# M306X.net
KiCad netlist of a schematic drawn in EAGLE
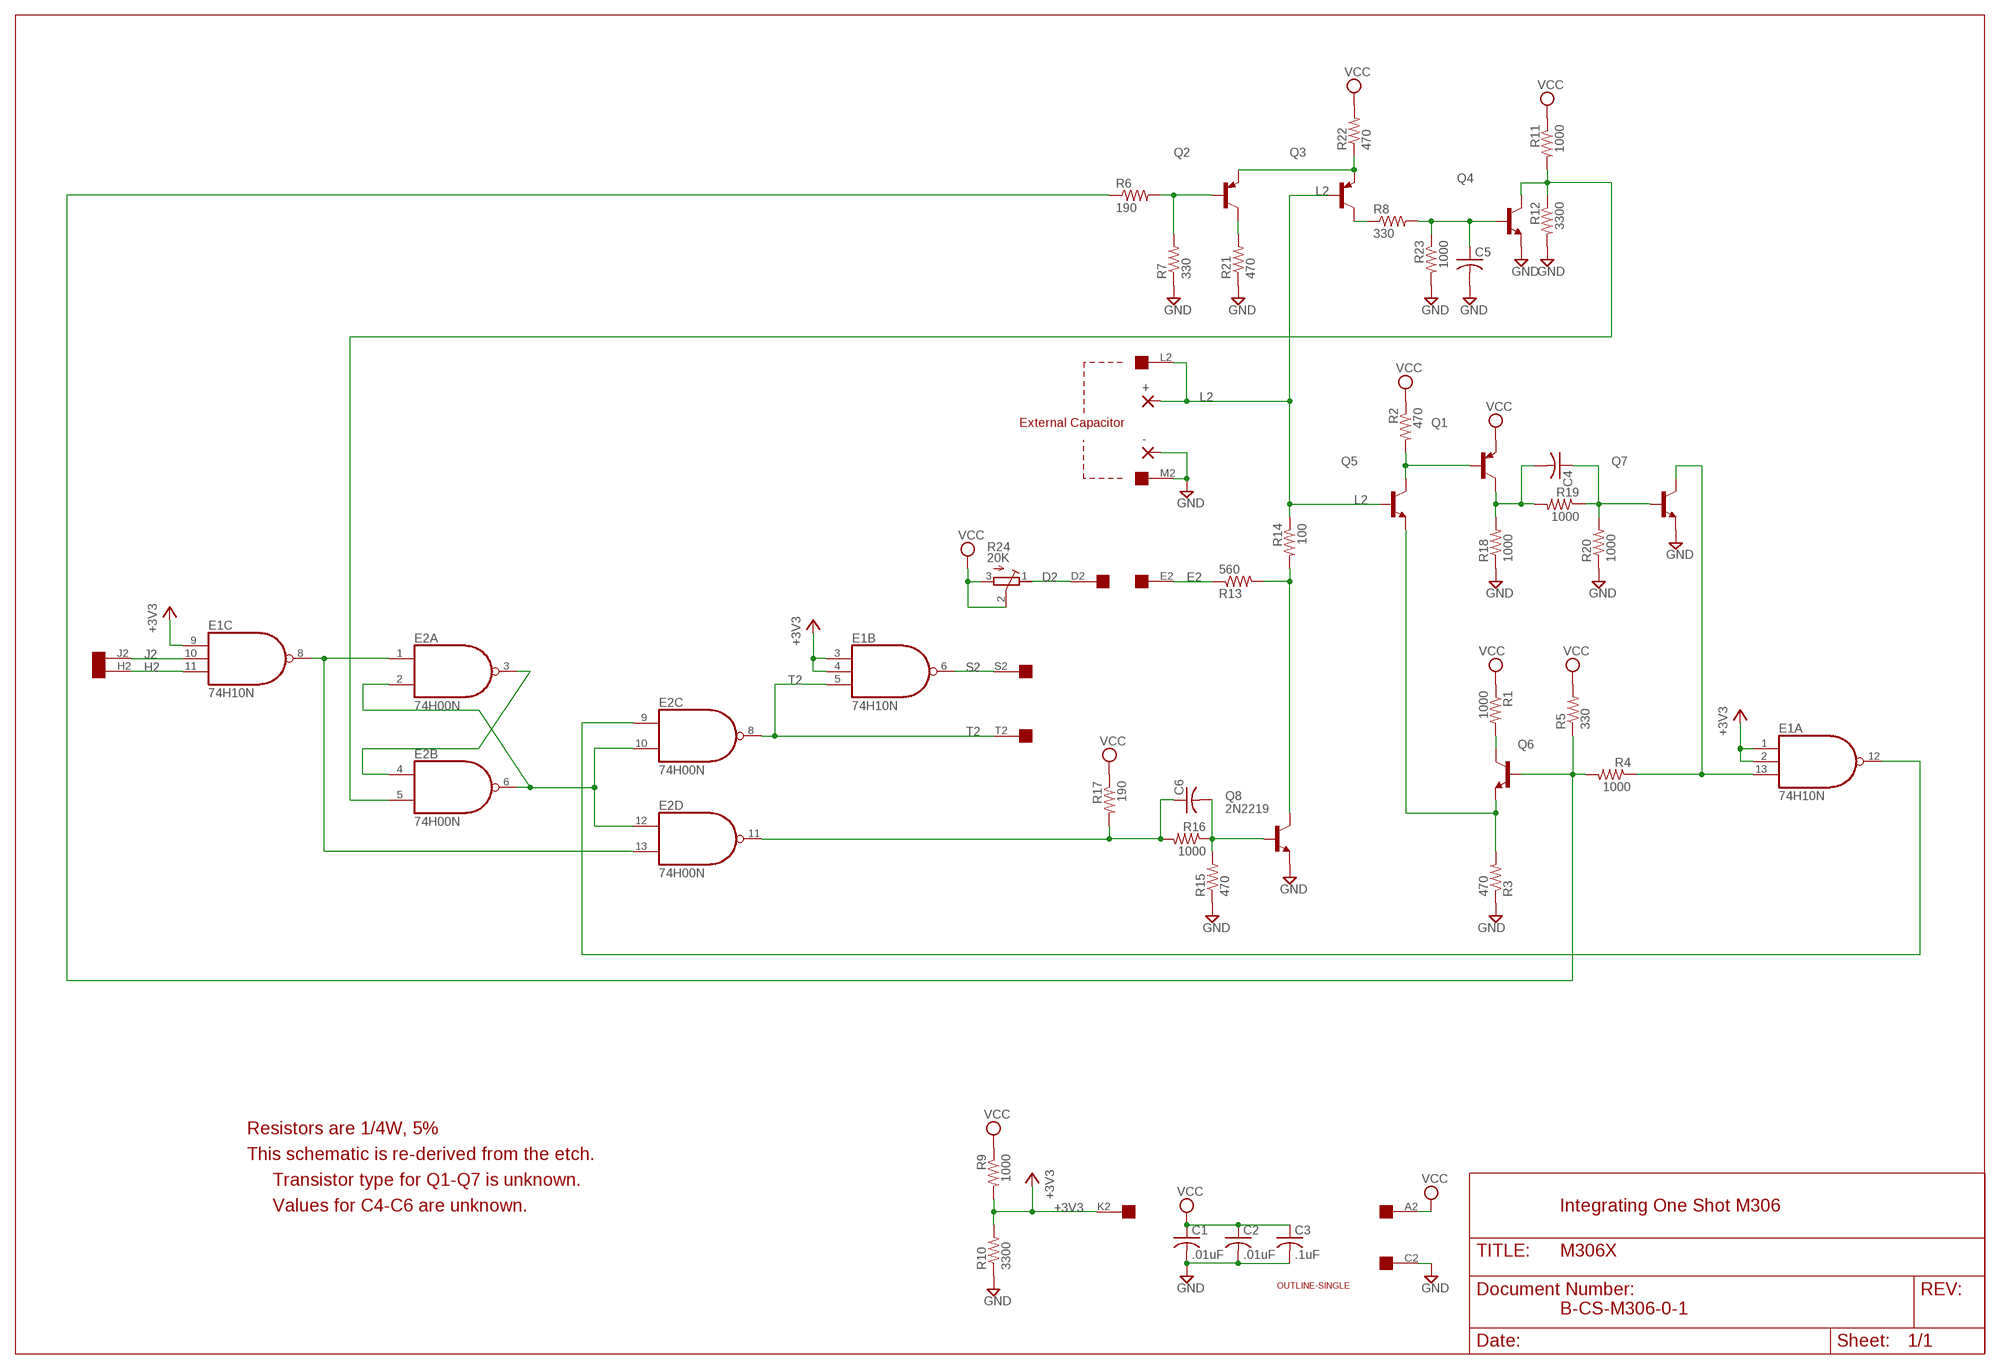
[diagram p0: schematic, sheet 1]

(export (version "E")
  (design (tool "Eeschema 10.0.6"))
  (components
    (comp (ref "+")
      (value "3,17/1,3")
      (footprint "eagle-import:3,17_1,3")
      (libsource (lib "eagle-import") (part "3,17/1,3"))
    )
    (comp (ref "-")
      (value "3,17/1,3")
      (footprint "eagle-import:3,17_1,3")
      (libsource (lib "eagle-import") (part "3,17/1,3"))
    )
    (comp (ref "C1")
      (value ".01uF")
      (footprint "eagle-import:C050-025X075")
      (libsource (lib "eagle-import") (part "C-US050-025X075"))
    )
    (comp (ref "C2")
      (value ".01uF")
      (footprint "eagle-import:C050-025X075")
      (libsource (lib "eagle-import") (part "C-US050-025X075"))
    )
    (comp (ref "C3")
      (value ".1uF")
      (footprint "eagle-import:C102-043X133")
      (libsource (lib "eagle-import") (part "C-US102-043X133"))
    )
    (comp (ref "C4")
      (value "C-US075-032X103")
      (footprint "eagle-import:C075-032X103")
      (libsource (lib "eagle-import") (part "C-US075-032X103"))
    )
    (comp (ref "C5")
      (value "C-US075-032X103")
      (footprint "eagle-import:C075-032X103")
      (libsource (lib "eagle-import") (part "C-US075-032X103"))
    )
    (comp (ref "C6")
      (value "C-US075-032X103")
      (footprint "eagle-import:C075-032X103")
      (libsource (lib "eagle-import") (part "C-US075-032X103"))
    )
    (comp (ref "E1")
      (value "74H10N")
      (footprint "eagle-import:DIL14")
      (libsource (lib "eagle-import") (part "7410N"))
    )
    (comp (ref "E2")
      (value "74H00N")
      (footprint "eagle-import:DIL14")
      (libsource (lib "eagle-import") (part "7400N"))
    )
    (comp (ref "Q1")
      (value "-PNP-TO5")
      (footprint "eagle-import:TO5")
      (libsource (lib "eagle-import") (part "-PNP-TO5"))
    )
    (comp (ref "Q2")
      (value "-PNP-TO5")
      (footprint "eagle-import:TO5")
      (libsource (lib "eagle-import") (part "-PNP-TO5"))
    )
    (comp (ref "Q3")
      (value "-PNP-TO5")
      (footprint "eagle-import:TO5")
      (libsource (lib "eagle-import") (part "-PNP-TO5"))
    )
    (comp (ref "Q4")
      (value "2N3019-NPN-TO39-EBC")
      (footprint "eagle-import:TO39")
      (libsource (lib "eagle-import") (part "-NPN-TO39-EBC2N3019"))
    )
    (comp (ref "Q5")
      (value "2N3019-NPN-TO39-EBC")
      (footprint "eagle-import:TO39")
      (libsource (lib "eagle-import") (part "-NPN-TO39-EBC2N3019"))
    )
    (comp (ref "Q6")
      (value "2N3019-NPN-TO39-EBC")
      (footprint "eagle-import:TO39")
      (libsource (lib "eagle-import") (part "-NPN-TO39-EBC2N3019"))
    )
    (comp (ref "Q7")
      (value "2N3019-NPN-TO39-EBC")
      (footprint "eagle-import:TO39")
      (libsource (lib "eagle-import") (part "-NPN-TO39-EBC2N3019"))
    )
    (comp (ref "Q8")
      (value "2N2219")
      (footprint "eagle-import:TO5")
      (libsource (lib "eagle-import") (part "2N2219"))
    )
    (comp (ref "R1")
      (value "1000")
      (footprint "eagle-import:0207_10")
      (libsource (lib "eagle-import") (part "R-US_0207/10"))
    )
    (comp (ref "R2")
      (value "470")
      (footprint "eagle-import:0207_10")
      (libsource (lib "eagle-import") (part "R-US_0207/10"))
    )
    (comp (ref "R3")
      (value "470")
      (footprint "eagle-import:0207_10")
      (libsource (lib "eagle-import") (part "R-US_0207/10"))
    )
    (comp (ref "R4")
      (value "1000")
      (footprint "eagle-import:0207_10")
      (libsource (lib "eagle-import") (part "R-US_0207/10"))
    )
    (comp (ref "R5")
      (value "330")
      (footprint "eagle-import:0207_10")
      (libsource (lib "eagle-import") (part "R-US_0207/10"))
    )
    (comp (ref "R6")
      (value "190")
      (footprint "eagle-import:0207_10")
      (libsource (lib "eagle-import") (part "R-US_0207/10"))
    )
    (comp (ref "R7")
      (value "330")
      (footprint "eagle-import:0207_10")
      (libsource (lib "eagle-import") (part "R-US_0207/10"))
    )
    (comp (ref "R8")
      (value "330")
      (footprint "eagle-import:0207_10")
      (libsource (lib "eagle-import") (part "R-US_0207/10"))
    )
    (comp (ref "R9")
      (value "1000")
      (footprint "eagle-import:0207_10")
      (libsource (lib "eagle-import") (part "R-US_0207/10"))
    )
    (comp (ref "R10")
      (value "3300")
      (footprint "eagle-import:0207_10")
      (libsource (lib "eagle-import") (part "R-US_0207/10"))
    )
    (comp (ref "R11")
      (value "1000")
      (footprint "eagle-import:0207_10")
      (libsource (lib "eagle-import") (part "R-US_0207/10"))
    )
    (comp (ref "R12")
      (value "3300")
      (footprint "eagle-import:0207_10")
      (libsource (lib "eagle-import") (part "R-US_0207/10"))
    )
    (comp (ref "R13")
      (value "560")
      (footprint "eagle-import:0207_10")
      (libsource (lib "eagle-import") (part "R-US_0207/10"))
    )
    (comp (ref "R14")
      (value "100")
      (footprint "eagle-import:0207_10")
      (libsource (lib "eagle-import") (part "R-US_0207/10"))
    )
    (comp (ref "R15")
      (value "470")
      (footprint "eagle-import:0207_10")
      (libsource (lib "eagle-import") (part "R-US_0207/10"))
    )
    (comp (ref "R16")
      (value "1000")
      (footprint "eagle-import:0207_10")
      (libsource (lib "eagle-import") (part "R-US_0207/10"))
    )
    (comp (ref "R17")
      (value "190")
      (footprint "eagle-import:0207_10")
      (libsource (lib "eagle-import") (part "R-US_0207/10"))
    )
    (comp (ref "R18")
      (value "1000")
      (footprint "eagle-import:0207_10")
      (libsource (lib "eagle-import") (part "R-US_0207/10"))
    )
    (comp (ref "R19")
      (value "1000")
      (footprint "eagle-import:0207_10")
      (libsource (lib "eagle-import") (part "R-US_0207/10"))
    )
    (comp (ref "R20")
      (value "1000")
      (footprint "eagle-import:0207_10")
      (libsource (lib "eagle-import") (part "R-US_0207/10"))
    )
    (comp (ref "R21")
      (value "470")
      (footprint "eagle-import:0207_10")
      (libsource (lib "eagle-import") (part "R-US_0207/10"))
    )
    (comp (ref "R22")
      (value "470")
      (footprint "eagle-import:0207_10")
      (libsource (lib "eagle-import") (part "R-US_0207/10"))
    )
    (comp (ref "R23")
      (value "1000")
      (footprint "eagle-import:0207_10")
      (libsource (lib "eagle-import") (part "R-US_0207/10"))
    )
    (comp (ref "R24")
      (value "20K")
      (footprint "eagle-import:3006Y")
      (libsource (lib "eagle-import") (part "275P"))
    )
    (comp (ref "U$1")
      (value "SINGLE")
      (footprint "eagle-import:EDGE-CON2")
      (libsource (lib "eagle-import") (part "SINGLE"))
    )
    (comp (ref "U$2")
      (value "OUTLINE-SINGLE")
      (footprint "eagle-import:SINGLE")
      (libsource (lib "eagle-import") (part "OUTLINE-SINGLE"))
    )
  )
  (nets
    (net (code "1") (name "+3V3") (class "Default")
      (node (ref "E1") (pin "1") (pinfunction "I0_1") (pintype "input"))
      (node (ref "E1") (pin "2") (pinfunction "I1_2") (pintype "input"))
      (node (ref "E1") (pin "3") (pinfunction "I0_3") (pintype "input"))
      (node (ref "E1") (pin "4") (pinfunction "I1_4") (pintype "input"))
      (node (ref "E1") (pin "9") (pinfunction "I0_9") (pintype "input"))
      (node (ref "R10") (pin "2") (pinfunction "2_2") (pintype "passive"))
      (node (ref "R9") (pin "2") (pinfunction "2_2") (pintype "passive"))
      (node (ref "U$1") (pin "K2") (pinfunction "1_K2") (pintype "bidirectional"))
    )
    (net (code "2") (name "/D2") (class "Default")
      (node (ref "R24") (pin "1") (pinfunction "A_1") (pintype "passive"))
      (node (ref "U$1") (pin "D2") (pinfunction "1_D2") (pintype "bidirectional"))
    )
    (net (code "3") (name "/E2") (class "Default")
      (node (ref "R13") (pin "1") (pinfunction "1_1") (pintype "passive"))
      (node (ref "U$1") (pin "E2") (pinfunction "1_E2") (pintype "bidirectional"))
    )
    (net (code "4") (name "/H2") (class "Default")
      (node (ref "E1") (pin "11") (pinfunction "I2_11") (pintype "input"))
      (node (ref "U$1") (pin "H2") (pinfunction "1_H2") (pintype "bidirectional"))
    )
    (net (code "5") (name "/J2") (class "Default")
      (node (ref "E1") (pin "10") (pinfunction "I1_10") (pintype "input"))
      (node (ref "U$1") (pin "J2") (pinfunction "1_J2") (pintype "bidirectional"))
    )
    (net (code "6") (name "/L2") (class "Default")
      (node (ref "+") (pin "1") (pinfunction "P_1") (pintype "passive"))
      (node (ref "Q3") (pin "2") (pinfunction "B_2") (pintype "passive"))
      (node (ref "Q5") (pin "2") (pinfunction "B_2") (pintype "passive"))
      (node (ref "R14") (pin "1") (pinfunction "1_1") (pintype "passive"))
      (node (ref "U$1") (pin "L2") (pinfunction "1_L2") (pintype "bidirectional"))
    )
    (net (code "7") (name "/S2") (class "Default")
      (node (ref "E1") (pin "6") (pinfunction "O_6") (pintype "output"))
      (node (ref "U$1") (pin "S2") (pinfunction "1_S2") (pintype "bidirectional"))
    )
    (net (code "8") (name "/T2") (class "Default")
      (node (ref "E1") (pin "5") (pinfunction "I2_5") (pintype "input"))
      (node (ref "E2") (pin "8") (pinfunction "O_8") (pintype "output"))
      (node (ref "U$1") (pin "T2") (pinfunction "1_T2") (pintype "bidirectional"))
    )
    (net (code "9") (name "GND") (class "Default")
      (node (ref "-") (pin "1") (pinfunction "P_1") (pintype "passive"))
      (node (ref "C1") (pin "2") (pinfunction "2_2") (pintype "passive"))
      (node (ref "C2") (pin "2") (pinfunction "2_2") (pintype "passive"))
      (node (ref "C3") (pin "2") (pinfunction "2_2") (pintype "passive"))
      (node (ref "C5") (pin "2") (pinfunction "2_2") (pintype "passive"))
      (node (ref "Q4") (pin "1") (pinfunction "E_1") (pintype "passive"))
      (node (ref "Q7") (pin "1") (pinfunction "E_1") (pintype "passive"))
      (node (ref "Q8") (pin "1") (pinfunction "E_1") (pintype "passive"))
      (node (ref "R10") (pin "1") (pinfunction "1_1") (pintype "passive"))
      (node (ref "R12") (pin "2") (pinfunction "2_2") (pintype "passive"))
      (node (ref "R15") (pin "1") (pinfunction "1_1") (pintype "passive"))
      (node (ref "R18") (pin "1") (pinfunction "1_1") (pintype "passive"))
      (node (ref "R20") (pin "1") (pinfunction "1_1") (pintype "passive"))
      (node (ref "R21") (pin "1") (pinfunction "1_1") (pintype "passive"))
      (node (ref "R23") (pin "2") (pinfunction "2_2") (pintype "passive"))
      (node (ref "R3") (pin "1") (pinfunction "1_1") (pintype "passive"))
      (node (ref "R7") (pin "1") (pinfunction "1_1") (pintype "passive"))
      (node (ref "U$1") (pin "C2") (pinfunction "1_C2") (pintype "bidirectional"))
      (node (ref "U$1") (pin "M2") (pinfunction "1_M2") (pintype "bidirectional"))
    )
    (net (code "10") (name "Net-(E1A-I2)") (class "Default")
      (node (ref "E1") (pin "13") (pinfunction "I2_13") (pintype "input"))
      (node (ref "Q7") (pin "3") (pinfunction "C_3") (pintype "passive"))
      (node (ref "R4") (pin "1") (pinfunction "1_1") (pintype "passive"))
    )
    (net (code "11") (name "Net-(E1A-O)") (class "Default")
      (node (ref "E1") (pin "12") (pinfunction "O_12") (pintype "output"))
      (node (ref "E2") (pin "9") (pinfunction "I0_9") (pintype "input"))
    )
    (net (code "12") (name "Net-(E1C-O)") (class "Default")
      (node (ref "E1") (pin "8") (pinfunction "O_8") (pintype "output"))
      (node (ref "E2") (pin "1") (pinfunction "I0_1") (pintype "input"))
      (node (ref "E2") (pin "13") (pinfunction "I1_13") (pintype "input"))
    )
    (net (code "13") (name "Net-(E2A-I1)") (class "Default")
      (node (ref "E2") (pin "10") (pinfunction "I1_10") (pintype "input"))
      (node (ref "E2") (pin "12") (pinfunction "I0_12") (pintype "input"))
      (node (ref "E2") (pin "2") (pinfunction "I1_2") (pintype "input"))
      (node (ref "E2") (pin "6") (pinfunction "O_6") (pintype "output"))
    )
    (net (code "14") (name "Net-(E2A-O)") (class "Default")
      (node (ref "E2") (pin "3") (pinfunction "O_3") (pintype "output"))
      (node (ref "E2") (pin "4") (pinfunction "I0_4") (pintype "input"))
    )
    (net (code "15") (name "Net-(E2B-I1)") (class "Default")
      (node (ref "E2") (pin "5") (pinfunction "I1_5") (pintype "input"))
      (node (ref "Q4") (pin "3") (pinfunction "C_3") (pintype "passive"))
      (node (ref "R11") (pin "2") (pinfunction "2_2") (pintype "passive"))
      (node (ref "R12") (pin "1") (pinfunction "1_1") (pintype "passive"))
    )
    (net (code "16") (name "Net-(E2D-O)") (class "Default")
      (node (ref "C6") (pin "1") (pinfunction "1_1") (pintype "passive"))
      (node (ref "E2") (pin "11") (pinfunction "O_11") (pintype "output"))
      (node (ref "R16") (pin "2") (pinfunction "2_2") (pintype "passive"))
      (node (ref "R17") (pin "2") (pinfunction "2_2") (pintype "passive"))
    )
    (net (code "17") (name "Net-(Q1-B)") (class "Default")
      (node (ref "Q1") (pin "2") (pinfunction "B_2") (pintype "passive"))
      (node (ref "Q5") (pin "3") (pinfunction "C_3") (pintype "passive"))
      (node (ref "R2") (pin "2") (pinfunction "2_2") (pintype "passive"))
    )
    (net (code "18") (name "Net-(Q1-C)") (class "Default")
      (node (ref "C4") (pin "2") (pinfunction "2_2") (pintype "passive"))
      (node (ref "Q1") (pin "3") (pinfunction "C_3") (pintype "passive"))
      (node (ref "R18") (pin "2") (pinfunction "2_2") (pintype "passive"))
      (node (ref "R19") (pin "2") (pinfunction "2_2") (pintype "passive"))
    )
    (net (code "19") (name "Net-(Q2-B)") (class "Default")
      (node (ref "Q2") (pin "2") (pinfunction "B_2") (pintype "passive"))
      (node (ref "R6") (pin "2") (pinfunction "2_2") (pintype "passive"))
      (node (ref "R7") (pin "2") (pinfunction "2_2") (pintype "passive"))
    )
    (net (code "20") (name "Net-(Q2-C)") (class "Default")
      (node (ref "Q2") (pin "3") (pinfunction "C_3") (pintype "passive"))
      (node (ref "R21") (pin "2") (pinfunction "2_2") (pintype "passive"))
    )
    (net (code "21") (name "Net-(Q2-E)") (class "Default")
      (node (ref "Q2") (pin "1") (pinfunction "E_1") (pintype "passive"))
      (node (ref "Q3") (pin "1") (pinfunction "E_1") (pintype "passive"))
      (node (ref "R22") (pin "1") (pinfunction "1_1") (pintype "passive"))
    )
    (net (code "22") (name "Net-(Q3-C)") (class "Default")
      (node (ref "Q3") (pin "3") (pinfunction "C_3") (pintype "passive"))
      (node (ref "R8") (pin "1") (pinfunction "1_1") (pintype "passive"))
    )
    (net (code "23") (name "Net-(Q4-B)") (class "Default")
      (node (ref "C5") (pin "1") (pinfunction "1_1") (pintype "passive"))
      (node (ref "Q4") (pin "2") (pinfunction "B_2") (pintype "passive"))
      (node (ref "R23") (pin "1") (pinfunction "1_1") (pintype "passive"))
      (node (ref "R8") (pin "2") (pinfunction "2_2") (pintype "passive"))
    )
    (net (code "24") (name "Net-(Q5-E)") (class "Default")
      (node (ref "Q5") (pin "1") (pinfunction "E_1") (pintype "passive"))
      (node (ref "Q6") (pin "1") (pinfunction "E_1") (pintype "passive"))
      (node (ref "R3") (pin "2") (pinfunction "2_2") (pintype "passive"))
    )
    (net (code "25") (name "Net-(Q6-B)") (class "Default")
      (node (ref "Q6") (pin "2") (pinfunction "B_2") (pintype "passive"))
      (node (ref "R4") (pin "2") (pinfunction "2_2") (pintype "passive"))
      (node (ref "R5") (pin "1") (pinfunction "1_1") (pintype "passive"))
      (node (ref "R6") (pin "1") (pinfunction "1_1") (pintype "passive"))
    )
    (net (code "26") (name "Net-(Q6-C)") (class "Default")
      (node (ref "Q6") (pin "3") (pinfunction "C_3") (pintype "passive"))
      (node (ref "R1") (pin "2") (pinfunction "2_2") (pintype "passive"))
    )
    (net (code "27") (name "Net-(Q7-B)") (class "Default")
      (node (ref "C4") (pin "1") (pinfunction "1_1") (pintype "passive"))
      (node (ref "Q7") (pin "2") (pinfunction "B_2") (pintype "passive"))
      (node (ref "R19") (pin "1") (pinfunction "1_1") (pintype "passive"))
      (node (ref "R20") (pin "2") (pinfunction "2_2") (pintype "passive"))
    )
    (net (code "28") (name "Net-(Q8-B)") (class "Default")
      (node (ref "C6") (pin "2") (pinfunction "2_2") (pintype "passive"))
      (node (ref "Q8") (pin "2") (pinfunction "B_2") (pintype "passive"))
      (node (ref "R15") (pin "2") (pinfunction "2_2") (pintype "passive"))
      (node (ref "R16") (pin "1") (pinfunction "1_1") (pintype "passive"))
    )
    (net (code "29") (name "Net-(Q8-C)") (class "Default")
      (node (ref "Q8") (pin "3") (pinfunction "C_3") (pintype "passive"))
      (node (ref "R13") (pin "2") (pinfunction "2_2") (pintype "passive"))
      (node (ref "R14") (pin "2") (pinfunction "2_2") (pintype "passive"))
    )
    (net (code "30") (name "VCC") (class "Default")
      (node (ref "C1") (pin "1") (pinfunction "1_1") (pintype "passive"))
      (node (ref "C2") (pin "1") (pinfunction "1_1") (pintype "passive"))
      (node (ref "C3") (pin "1") (pinfunction "1_1") (pintype "passive"))
      (node (ref "Q1") (pin "1") (pinfunction "E_1") (pintype "passive"))
      (node (ref "R1") (pin "1") (pinfunction "1_1") (pintype "passive"))
      (node (ref "R11") (pin "1") (pinfunction "1_1") (pintype "passive"))
      (node (ref "R17") (pin "1") (pinfunction "1_1") (pintype "passive"))
      (node (ref "R2") (pin "1") (pinfunction "1_1") (pintype "passive"))
      (node (ref "R22") (pin "2") (pinfunction "2_2") (pintype "passive"))
      (node (ref "R24") (pin "2") (pinfunction "S_2") (pintype "passive"))
      (node (ref "R24") (pin "3") (pinfunction "E_3") (pintype "passive"))
      (node (ref "R5") (pin "2") (pinfunction "2_2") (pintype "passive"))
      (node (ref "R9") (pin "1") (pinfunction "1_1") (pintype "passive"))
      (node (ref "U$1") (pin "A2") (pinfunction "1_A2") (pintype "bidirectional"))
    )
  )
)
